# BMC.net
KiCad netlist of a schematic drawn in Altium Designer
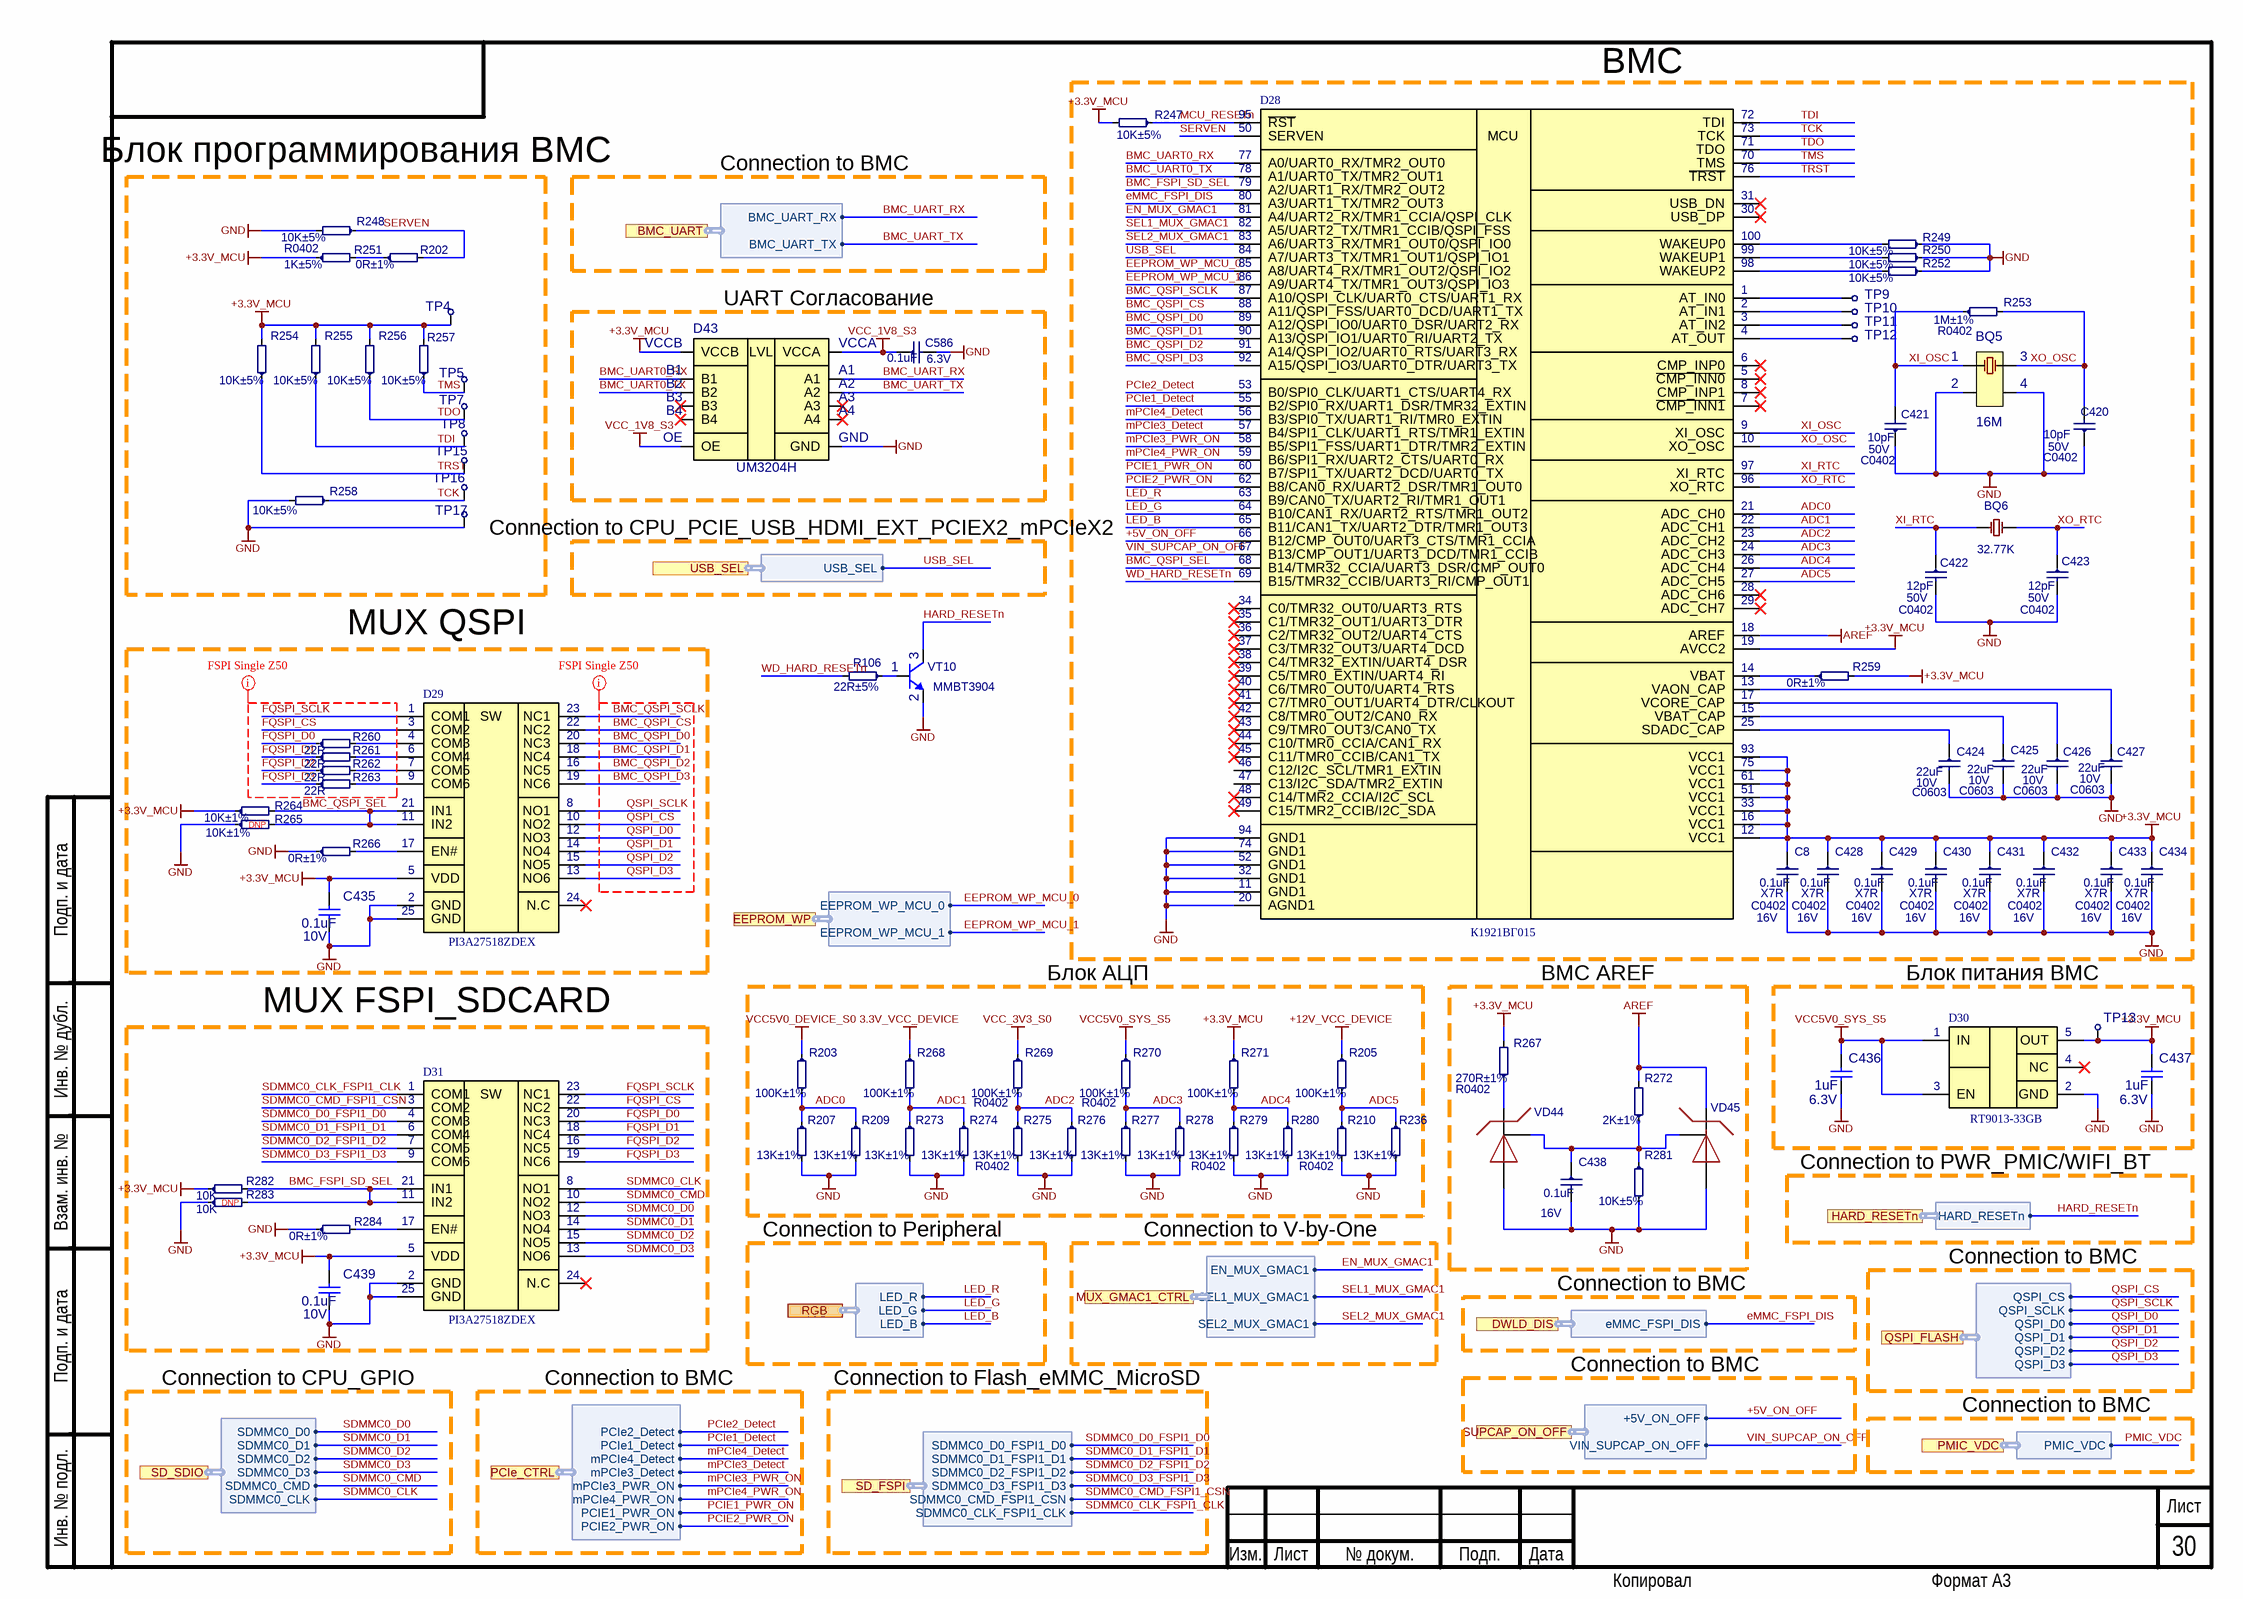
[diagram p0: BMC.SchDoc]

(export (version "E")
  (design (tool "Eeschema 10.0.6"))
  (components
    (comp (ref "BQ5")
      (value "16M")
      (footprint "NX3225GA")
      (description "16MHz 3225 quartz")
      (fields (field (name "PART NUMBER") "X322516MLB4SI") (field (name "TOLERANCE") "30ppm"))
      (libsource (lib "ATB") (part "BQ_4pin_2closed_2.4_2.4"))
    )
    (comp (ref "BQ6")
      (value "32.77K")
      (footprint "FC-12M")
      (description "CRYSTAL 32.768KHZ 12.5PF SMD")
      (fields (field (name "PART NUMBER") "NX2012SA-32.768K-STD-MUB-1") (field (name "MANUFACTURER") "NDK"))
      (libsource (lib "ATB") (part "BQ"))
    )
    (comp (ref "C8")
      (value "0.1uF")
      (footprint "C0402")
      (description "Ceramic Capacitor 0402 100nF ±5% 16V X7R")
      (fields
        (field (name "DIELECTRIC") "X7R")
        (field (name "VOLTAGE") "16V")
        (field (name "CASE") "C0402")
        (field (name "PART NUMBER") "0402-X7R-16V-0.1uF±10%")
        (field (name "TOLERANCE") "10%")
      )
      (libsource (lib "ATB") (part "C"))
    )
    (comp (ref "C420")
      (value "10pF")
      (footprint "C0402")
      (fields
        (field (name "VOLTAGE") "50V")
        (field (name "CASE") "C0402")
        (field (name "PART NUMBER") "0402-NP0-50V-10pF±5%")
        (field (name "TOLERANCE") "5%")
        (field (name "MANUFACTURER") "Yageo")
      )
      (libsource (lib "ATB") (part "C"))
    )
    (comp (ref "C421")
      (value "10pF")
      (footprint "C0402")
      (fields
        (field (name "VOLTAGE") "50V")
        (field (name "CASE") "C0402")
        (field (name "PART NUMBER") "0402-NP0-50V-10pF±5%")
        (field (name "TOLERANCE") "5%")
        (field (name "MANUFACTURER") "Yageo")
      )
      (libsource (lib "ATB") (part "C"))
    )
    (comp (ref "C422")
      (value "12pF")
      (footprint "C0402")
      (fields
        (field (name "VOLTAGE") "50V")
        (field (name "CASE") "C0402")
        (field (name "PART NUMBER") "0402-NP0-50V-12pF±5%")
        (field (name "TOLERANCE") "5%")
        (field (name "MANUFACTURER") "Murata Electronics")
      )
      (libsource (lib "ATB") (part "C"))
    )
    (comp (ref "C423")
      (value "12pF")
      (footprint "C0402")
      (fields
        (field (name "VOLTAGE") "50V")
        (field (name "CASE") "C0402")
        (field (name "PART NUMBER") "0402-NP0-50V-12pF±5%")
        (field (name "TOLERANCE") "5%")
        (field (name "MANUFACTURER") "Murata Electronics")
      )
      (libsource (lib "ATB") (part "C"))
    )
    (comp (ref "C424")
      (value "22uF")
      (footprint "C0603")
      (fields
        (field (name "VOLTAGE") "10V")
        (field (name "CASE") "C0603")
        (field (name "PART NUMBER") "0603-X5R-10V-22uF±20%")
        (field (name "TOLERANCE") "20%")
        (field (name "MANUFACTURER") "Samsung Electro-Mechanics")
      )
      (libsource (lib "ATB") (part "C"))
    )
    (comp (ref "C425")
      (value "22uF")
      (footprint "C0603")
      (fields
        (field (name "VOLTAGE") "10V")
        (field (name "CASE") "C0603")
        (field (name "PART NUMBER") "0603-X5R-10V-22uF±20%")
        (field (name "TOLERANCE") "20%")
        (field (name "MANUFACTURER") "Samsung Electro-Mechanics")
      )
      (libsource (lib "ATB") (part "C"))
    )
    (comp (ref "C426")
      (value "22uF")
      (footprint "C0603")
      (fields
        (field (name "VOLTAGE") "10V")
        (field (name "CASE") "C0603")
        (field (name "PART NUMBER") "0603-X5R-10V-22uF±20%")
        (field (name "TOLERANCE") "20%")
        (field (name "MANUFACTURER") "Samsung Electro-Mechanics")
      )
      (libsource (lib "ATB") (part "C"))
    )
    (comp (ref "C427")
      (value "22uF")
      (footprint "C0603")
      (fields
        (field (name "VOLTAGE") "10V")
        (field (name "CASE") "C0603")
        (field (name "PART NUMBER") "0603-X5R-10V-22uF±20%")
        (field (name "TOLERANCE") "20%")
        (field (name "MANUFACTURER") "Samsung Electro-Mechanics")
      )
      (libsource (lib "ATB") (part "C"))
    )
    (comp (ref "C428")
      (value "0.1uF")
      (footprint "C0402")
      (description "Ceramic Capacitor 0402 100nF ±5% 16V X7R")
      (fields
        (field (name "DIELECTRIC") "X7R")
        (field (name "VOLTAGE") "16V")
        (field (name "CASE") "C0402")
        (field (name "PART NUMBER") "0402-X7R-16V-0.1uF±10%")
        (field (name "TOLERANCE") "10%")
      )
      (libsource (lib "ATB") (part "C"))
    )
    (comp (ref "C429")
      (value "0.1uF")
      (footprint "C0402")
      (description "Ceramic Capacitor 0402 100nF ±5% 16V X7R")
      (fields
        (field (name "DIELECTRIC") "X7R")
        (field (name "VOLTAGE") "16V")
        (field (name "CASE") "C0402")
        (field (name "PART NUMBER") "0402-X7R-16V-0.1uF±10%")
        (field (name "TOLERANCE") "10%")
      )
      (libsource (lib "ATB") (part "C"))
    )
    (comp (ref "C430")
      (value "0.1uF")
      (footprint "C0402")
      (description "Ceramic Capacitor 0402 100nF ±5% 16V X7R")
      (fields
        (field (name "DIELECTRIC") "X7R")
        (field (name "VOLTAGE") "16V")
        (field (name "CASE") "C0402")
        (field (name "PART NUMBER") "0402-X7R-16V-0.1uF±10%")
        (field (name "TOLERANCE") "10%")
      )
      (libsource (lib "ATB") (part "C"))
    )
    (comp (ref "C431")
      (value "0.1uF")
      (footprint "C0402")
      (description "Ceramic Capacitor 0402 100nF ±5% 16V X7R")
      (fields
        (field (name "DIELECTRIC") "X7R")
        (field (name "VOLTAGE") "16V")
        (field (name "CASE") "C0402")
        (field (name "PART NUMBER") "0402-X7R-16V-0.1uF±10%")
        (field (name "TOLERANCE") "10%")
      )
      (libsource (lib "ATB") (part "C"))
    )
    (comp (ref "C432")
      (value "0.1uF")
      (footprint "C0402")
      (description "Ceramic Capacitor 0402 100nF ±5% 16V X7R")
      (fields
        (field (name "DIELECTRIC") "X7R")
        (field (name "VOLTAGE") "16V")
        (field (name "CASE") "C0402")
        (field (name "PART NUMBER") "0402-X7R-16V-0.1uF±10%")
        (field (name "TOLERANCE") "10%")
      )
      (libsource (lib "ATB") (part "C"))
    )
    (comp (ref "C433")
      (value "0.1uF")
      (footprint "C0402")
      (description "Ceramic Capacitor 0402 100nF ±5% 16V X7R")
      (fields
        (field (name "DIELECTRIC") "X7R")
        (field (name "VOLTAGE") "16V")
        (field (name "CASE") "C0402")
        (field (name "PART NUMBER") "0402-X7R-16V-0.1uF±10%")
        (field (name "TOLERANCE") "10%")
      )
      (libsource (lib "ATB") (part "C"))
    )
    (comp (ref "C434")
      (value "0.1uF")
      (footprint "C0402")
      (description "Ceramic Capacitor 0402 100nF ±5% 16V X7R")
      (fields
        (field (name "DIELECTRIC") "X7R")
        (field (name "VOLTAGE") "16V")
        (field (name "CASE") "C0402")
        (field (name "PART NUMBER") "0402-X7R-16V-0.1uF±10%")
        (field (name "TOLERANCE") "10%")
      )
      (libsource (lib "ATB") (part "C"))
    )
    (comp (ref "C435")
      (value "0.1uF")
      (footprint "C0402")
      (fields
        (field (name "PART NUMBER") "0402-X5R-10V-0.1uF±10%")
        (field (name "VOLTAGE") "10V")
        (field (name "TOLERANCE") "10%")
        (field (name "MANUFACTURER") "Yageo")
      )
      (libsource (lib "") (part "C_1"))
    )
    (comp (ref "C436")
      (value "1uF")
      (footprint "C0402")
      (fields
        (field (name "PART NUMBER") "0402-X7R-6.3V-1uF±10%")
        (field (name "VOLTAGE") "6.3V")
        (field (name "TOLERANCE") "10%")
        (field (name "MANUFACTURER") "Yageo")
      )
      (libsource (lib "") (part "C_1"))
    )
    (comp (ref "C437")
      (value "1uF")
      (footprint "C0402")
      (fields
        (field (name "PART NUMBER") "0402-X7R-6.3V-1uF±10%")
        (field (name "VOLTAGE") "6.3V")
        (field (name "TOLERANCE") "10%")
        (field (name "MANUFACTURER") "Yageo")
      )
      (libsource (lib "") (part "C_1"))
    )
    (comp (ref "C438")
      (value "0.1uF")
      (footprint "C0402")
      (description "Ceramic Capacitor 0402 100nF ±5% 16V X7R")
      (fields
        (field (name "VOLTAGE") "16V")
        (field (name "PART NUMBER") "0402-X7R-16V-0.1uF±10%")
        (field (name "TOLERANCE") "10%")
      )
      (libsource (lib "ATB") (part "C"))
    )
    (comp (ref "C439")
      (value "0.1uF")
      (footprint "C0402")
      (fields
        (field (name "PART NUMBER") "0402-X5R-10V-0.1uF±10%")
        (field (name "VOLTAGE") "10V")
        (field (name "TOLERANCE") "10%")
        (field (name "MANUFACTURER") "Yageo")
      )
      (libsource (lib "") (part "C_1"))
    )
    (comp (ref "C586")
      (value "0.1uF")
      (footprint "C0201")
      (fields
        (field (name "VOLTAGE") "6.3V")
        (field (name "PART NUMBER") "0201-X5R-6.3V-0.1uF±10%")
        (field (name "TOLERANCE") "10%")
        (field (name "MANUFACTURER") "Yageo")
      )
      (libsource (lib "ATB") (part "C"))
    )
    (comp (ref "D28")
      (value "К1921ВГ015")
      (footprint "К1921ВГ015")
      (description "32-разрядный ультранизкопотребляющий микроконтроллер RISС-V в пластиковом корпусе.")
      (fields (field (name "MANUFACTURER") "НИИЭТ"))
      (libsource (lib "LIB_RK") (part "К1921ВГ015"))
    )
    (comp (ref "D29")
      (value "PI3A27518ZDEX")
      (footprint "PI3A27518ZDEX")
      (description "1.8/3.3V High-Bandwidth 6-channel, 2:1 Mux/DeMux")
      (fields (field (name "MANUFACTURER") "Diodes Incorporated"))
      (libsource (lib "LIB_RK") (part "PI3A27518ZDEX"))
    )
    (comp (ref "D30")
      (value "RT9013-33GB")
      (footprint "RT9013-25GB")
      (description "Linear Voltage Regulators   500mA 50dB@(10kHz) Fixed 3.3V")
      (fields (field (name "MANUFACTURER") "Richtek"))
      (libsource (lib "LIB_RK") (part "RT9013-25GB"))
    )
    (comp (ref "D31")
      (value "PI3A27518ZDEX")
      (footprint "PI3A27518ZDEX")
      (description "1.8/3.3V High-Bandwidth 6-channel, 2:1 Mux/DeMux")
      (fields (field (name "MANUFACTURER") "Diodes Incorporated"))
      (libsource (lib "LIB_RK") (part "PI3A27518ZDEX"))
    )
    (comp (ref "D43")
      (value "UM3204H")
      (footprint "UM3204H")
      (description "CSP-12(1.4x1.9) Translators, Level Shifters ROHS")
      (fields (field (name "MANUFACTURER") "Union"))
      (libsource (lib "LIB_RK") (part "UM3204H"))
    )
    (comp (ref "R106")
      (value "22R±5%")
      (footprint "R0402")
      (fields
        (field (name "PART NUMBER") "0402-0.0625W-22R-100ppm±5%")
        (field (name "TOLERANCE") "5%")
        (field (name "MANUFACTURER") "Yageo")
      )
      (libsource (lib "ATB") (part "R"))
    )
    (comp (ref "R202")
      (value "0R±1%")
      (footprint "R0402")
      (description "Chip Resistor 0402 0Ω ±1% 50V ±100ppm/℃ Thick Film")
      (fields (field (name "PART NUMBER") "0402-0.0625W-0R-100ppm±1%") (field (name "TOLERANCE") "1%"))
      (libsource (lib "ATB") (part "R"))
    )
    (comp (ref "R203")
      (value "100K±1%")
      (footprint "R0402")
      (description "Chip Resistor 0402 100kΩ ±1% 50V ±100ppm/℃ Thick Film")
      (fields (field (name "PART NUMBER") "0402-0.0625W-100K-100ppm±1%") (field (name "TOLERANCE") "1%"))
      (libsource (lib "ATB") (part "R"))
    )
    (comp (ref "R205")
      (value "100K±1%")
      (footprint "R0402")
      (description "Chip Resistor 0402 100kΩ ±1% 50V ±100ppm/℃ Thick Film")
      (fields (field (name "PART NUMBER") "0402-0.0625W-100K-100ppm±1%") (field (name "TOLERANCE") "1%"))
      (libsource (lib "ATB") (part "R"))
    )
    (comp (ref "R207")
      (value "13K±1%")
      (footprint "R0402")
      (fields
        (field (name "PART NUMBER") "0402-0.0625W-13K-100ppm±1%")
        (field (name "TOLERANCE") "1%")
        (field (name "MANUFACTURER") "Yageo")
      )
      (libsource (lib "ATB") (part "R"))
    )
    (comp (ref "R209")
      (value "13K±1%")
      (footprint "R0402")
      (fields
        (field (name "PART NUMBER") "0402-0.0625W-13K-100ppm±1%")
        (field (name "TOLERANCE") "1%")
        (field (name "MANUFACTURER") "Yageo")
      )
      (libsource (lib "ATB") (part "R"))
    )
    (comp (ref "R210")
      (value "13K±1%")
      (footprint "R0402")
      (fields
        (field (name "CASE") "R0402")
        (field (name "PART NUMBER") "0402-0.0625W-13K-100ppm±1%")
        (field (name "TOLERANCE") "1%")
        (field (name "MANUFACTURER") "Yageo")
      )
      (libsource (lib "ATB") (part "R"))
    )
    (comp (ref "R236")
      (value "13K±1%")
      (footprint "R0402")
      (fields
        (field (name "PART NUMBER") "0402-0.0625W-13K-100ppm±1%")
        (field (name "TOLERANCE") "1%")
        (field (name "MANUFACTURER") "Yageo")
      )
      (libsource (lib "ATB") (part "R"))
    )
    (comp (ref "R247")
      (value "10K±5%")
      (footprint "R0402")
      (fields
        (field (name "PART NUMBER") "0402-0.0625W-10K-100ppm±5%")
        (field (name "TOLERANCE") "5%")
        (field (name "MANUFACTURER") "Yageo")
      )
      (libsource (lib "ATB") (part "R"))
    )
    (comp (ref "R248")
      (value "10K±5%")
      (footprint "R0402")
      (fields
        (field (name "CASE") "R0402")
        (field (name "PART NUMBER") "0402-0.0625W-10K-100ppm±5%")
        (field (name "TOLERANCE") "5%")
        (field (name "MANUFACTURER") "Yageo")
      )
      (libsource (lib "ATB") (part "R"))
    )
    (comp (ref "R249")
      (value "10K±5%")
      (footprint "R0402")
      (fields
        (field (name "PART NUMBER") "0402-0.0625W-10K-100ppm±5%")
        (field (name "TOLERANCE") "5%")
        (field (name "MANUFACTURER") "Yageo")
      )
      (libsource (lib "ATB") (part "R"))
    )
    (comp (ref "R250")
      (value "10K±5%")
      (footprint "R0402")
      (fields
        (field (name "PART NUMBER") "0402-0.0625W-10K-100ppm±5%")
        (field (name "TOLERANCE") "5%")
        (field (name "MANUFACTURER") "Yageo")
      )
      (libsource (lib "ATB") (part "R"))
    )
    (comp (ref "R251")
      (value "1K±5%")
      (footprint "R0402")
      (fields
        (field (name "PART NUMBER") "0402-0.0625W-1K-100ppm±5%")
        (field (name "TOLERANCE") "5%")
        (field (name "MANUFACTURER") "Yageo")
      )
      (libsource (lib "ATB") (part "R"))
    )
    (comp (ref "R252")
      (value "10K±5%")
      (footprint "R0402")
      (fields
        (field (name "PART NUMBER") "0402-0.0625W-10K-100ppm±5%")
        (field (name "TOLERANCE") "5%")
        (field (name "MANUFACTURER") "Yageo")
      )
      (libsource (lib "ATB") (part "R"))
    )
    (comp (ref "R253")
      (value "1M±1%")
      (footprint "R0402")
      (description "Chip Resistor 0402 1MΩ ±1% 50V ±100ppm/℃ Thick Film")
      (fields
        (field (name "CASE") "R0402")
        (field (name "PART NUMBER") "0402-0.0625W-1M-100ppm±1%")
        (field (name "TOLERANCE") "1%")
      )
      (libsource (lib "ATB") (part "R"))
    )
    (comp (ref "R254")
      (value "10K±5%")
      (footprint "R0402")
      (fields
        (field (name "PART NUMBER") "0402-0.0625W-10K-100ppm±5%")
        (field (name "TOLERANCE") "5%")
        (field (name "MANUFACTURER") "Yageo")
      )
      (libsource (lib "ATB") (part "R"))
    )
    (comp (ref "R255")
      (value "10K±5%")
      (footprint "R0402")
      (fields
        (field (name "PART NUMBER") "0402-0.0625W-10K-100ppm±5%")
        (field (name "TOLERANCE") "5%")
        (field (name "MANUFACTURER") "Yageo")
      )
      (libsource (lib "ATB") (part "R"))
    )
    (comp (ref "R256")
      (value "10K±5%")
      (footprint "R0402")
      (fields
        (field (name "PART NUMBER") "0402-0.0625W-10K-100ppm±5%")
        (field (name "TOLERANCE") "5%")
        (field (name "MANUFACTURER") "Yageo")
      )
      (libsource (lib "ATB") (part "R"))
    )
    (comp (ref "R257")
      (value "10K±5%")
      (footprint "R0402")
      (fields
        (field (name "PART NUMBER") "0402-0.0625W-10K-100ppm±5%")
        (field (name "TOLERANCE") "5%")
        (field (name "MANUFACTURER") "Yageo")
      )
      (libsource (lib "ATB") (part "R"))
    )
    (comp (ref "R258")
      (value "10K±5%")
      (footprint "R0402")
      (fields
        (field (name "PART NUMBER") "0402-0.0625W-10K-100ppm±5%")
        (field (name "TOLERANCE") "5%")
        (field (name "MANUFACTURER") "Yageo")
      )
      (libsource (lib "ATB") (part "R"))
    )
    (comp (ref "R259")
      (value "0R±1%")
      (footprint "R0402")
      (description "Chip Resistor 0402 0Ω ±1% 50V ±100ppm/℃ Thick Film")
      (fields (field (name "PART NUMBER") "0402-0.0625W-0R-100ppm±1%") (field (name "TOLERANCE") "1%"))
      (libsource (lib "ATB") (part "R"))
    )
    (comp (ref "R260")
      (value "22R")
      (footprint "R0402")
      (description "Chip Resistor 0402 22Ω ±1% 50V ±100ppm/℃ Thick Film")
      (fields (field (name "PART NUMBER") "0402-0.0625W-22R-100ppm±1%") (field (name "TOLERANCE") "1%"))
      (libsource (lib "ATB") (part "R"))
    )
    (comp (ref "R261")
      (value "22R")
      (footprint "R0402")
      (description "Chip Resistor 0402 22Ω ±1% 50V ±100ppm/℃ Thick Film")
      (fields (field (name "PART NUMBER") "0402-0.0625W-22R-100ppm±1%") (field (name "TOLERANCE") "1%"))
      (libsource (lib "ATB") (part "R"))
    )
    (comp (ref "R262")
      (value "22R")
      (footprint "R0402")
      (description "Chip Resistor 0402 22Ω ±1% 50V ±100ppm/℃ Thick Film")
      (fields (field (name "PART NUMBER") "0402-0.0625W-22R-100ppm±1%") (field (name "TOLERANCE") "1%"))
      (libsource (lib "ATB") (part "R"))
    )
    (comp (ref "R263")
      (value "22R")
      (footprint "R0402")
      (description "Chip Resistor 0402 22Ω ±1% 50V ±100ppm/℃ Thick Film")
      (fields (field (name "PART NUMBER") "0402-0.0625W-22R-100ppm±1%") (field (name "TOLERANCE") "1%"))
      (libsource (lib "ATB") (part "R"))
    )
    (comp (ref "R264")
      (value "10K±1%")
      (footprint "R0402")
      (description "Chip Resistor 0402 10kΩ ±1% 50V ±100ppm/℃ Thick Film")
      (fields (field (name "PART NUMBER") "0402-0.0625W-10K-100ppm±1%") (field (name "TOLERANCE") "1%"))
      (libsource (lib "ATB") (part "R"))
    )
    (comp (ref "R265")
      (value "10K±1%")
      (footprint "R0402")
      (description "Chip Resistor 0402 10kΩ ±1% 50V ±100ppm/℃ Thick Film")
      (fields (field (name "PART NUMBER") "0402-0.0625W-10K-100ppm±1%") (field (name "TOLERANCE") "1%"))
      (libsource (lib "ATB") (part "R"))
    )
    (comp (ref "R266")
      (value "0R±1%")
      (footprint "R0402")
      (description "Chip Resistor 0402 0Ω ±1% 50V ±100ppm/℃ Thick Film")
      (fields (field (name "PART NUMBER") "0402-0.0625W-0R-100ppm±1%") (field (name "TOLERANCE") "1%"))
      (libsource (lib "ATB") (part "R"))
    )
    (comp (ref "R267")
      (value "270R±1%")
      (footprint "R0402")
      (fields
        (field (name "CASE") "R0402")
        (field (name "PART NUMBER") "0402-0.0625W-270R-100ppm±1%")
        (field (name "TOLERANCE") "1%")
        (field (name "MANUFACTURER") "UNI-ROYAL")
      )
      (libsource (lib "ATB") (part "R"))
    )
    (comp (ref "R268")
      (value "100K±1%")
      (footprint "R0402")
      (description "Chip Resistor 0402 100kΩ ±1% 50V ±100ppm/℃ Thick Film")
      (fields (field (name "PART NUMBER") "0402-0.0625W-100K-100ppm±1%") (field (name "TOLERANCE") "1%"))
      (libsource (lib "ATB") (part "R"))
    )
    (comp (ref "R269")
      (value "100K±1%")
      (footprint "R0402")
      (description "Chip Resistor 0402 100kΩ ±1% 50V ±100ppm/℃ Thick Film")
      (fields
        (field (name "CASE") "R0402")
        (field (name "PART NUMBER") "0402-0.0625W-100K-100ppm±1%")
        (field (name "TOLERANCE") "1%")
      )
      (libsource (lib "ATB") (part "R"))
    )
    (comp (ref "R270")
      (value "100K±1%")
      (footprint "R0402")
      (description "Chip Resistor 0402 100kΩ ±1% 50V ±100ppm/℃ Thick Film")
      (fields
        (field (name "CASE") "R0402")
        (field (name "PART NUMBER") "0402-0.0625W-100K-100ppm±1%")
        (field (name "TOLERANCE") "1%")
      )
      (libsource (lib "ATB") (part "R"))
    )
    (comp (ref "R271")
      (value "100K±1%")
      (footprint "R0402")
      (description "Chip Resistor 0402 100kΩ ±1% 50V ±100ppm/℃ Thick Film")
      (fields (field (name "PART NUMBER") "0402-0.0625W-100K-100ppm±1%") (field (name "TOLERANCE") "1%"))
      (libsource (lib "ATB") (part "R"))
    )
    (comp (ref "R272")
      (value "2K±1%")
      (footprint "R0402")
      (fields
        (field (name "PART NUMBER") "0402-0.0625W-2K-100ppm±1%")
        (field (name "TOLERANCE") "1%")
        (field (name "MANUFACTURER") "Yageo")
      )
      (libsource (lib "ATB") (part "R"))
    )
    (comp (ref "R273")
      (value "13K±1%")
      (footprint "R0402")
      (fields
        (field (name "PART NUMBER") "0402-0.0625W-13K-100ppm±1%")
        (field (name "TOLERANCE") "1%")
        (field (name "MANUFACTURER") "Yageo")
      )
      (libsource (lib "ATB") (part "R"))
    )
    (comp (ref "R274")
      (value "13K±1%")
      (footprint "R0402")
      (fields
        (field (name "PART NUMBER") "0402-0.0625W-13K-100ppm±1%")
        (field (name "TOLERANCE") "1%")
        (field (name "MANUFACTURER") "Yageo")
      )
      (libsource (lib "ATB") (part "R"))
    )
    (comp (ref "R275")
      (value "13K±1%")
      (footprint "R0402")
      (fields
        (field (name "CASE") "R0402")
        (field (name "PART NUMBER") "0402-0.0625W-13K-100ppm±1%")
        (field (name "TOLERANCE") "1%")
        (field (name "MANUFACTURER") "Yageo")
      )
      (libsource (lib "ATB") (part "R"))
    )
    (comp (ref "R276")
      (value "13K±1%")
      (footprint "R0402")
      (fields
        (field (name "PART NUMBER") "0402-0.0625W-13K-100ppm±1%")
        (field (name "TOLERANCE") "1%")
        (field (name "MANUFACTURER") "Yageo")
      )
      (libsource (lib "ATB") (part "R"))
    )
    (comp (ref "R277")
      (value "13K±1%")
      (footprint "R0402")
      (fields
        (field (name "PART NUMBER") "0402-0.0625W-13K-100ppm±1%")
        (field (name "TOLERANCE") "1%")
        (field (name "MANUFACTURER") "Yageo")
      )
      (libsource (lib "ATB") (part "R"))
    )
    (comp (ref "R278")
      (value "13K±1%")
      (footprint "R0402")
      (fields
        (field (name "PART NUMBER") "0402-0.0625W-13K-100ppm±1%")
        (field (name "TOLERANCE") "1%")
        (field (name "MANUFACTURER") "Yageo")
      )
      (libsource (lib "ATB") (part "R"))
    )
    (comp (ref "R279")
      (value "13K±1%")
      (footprint "R0402")
      (fields
        (field (name "CASE") "R0402")
        (field (name "PART NUMBER") "0402-0.0625W-13K-100ppm±1%")
        (field (name "TOLERANCE") "1%")
        (field (name "MANUFACTURER") "Yageo")
      )
      (libsource (lib "ATB") (part "R"))
    )
    (comp (ref "R280")
      (value "13K±1%")
      (footprint "R0402")
      (fields
        (field (name "PART NUMBER") "0402-0.0625W-13K-100ppm±1%")
        (field (name "TOLERANCE") "1%")
        (field (name "MANUFACTURER") "Yageo")
      )
      (libsource (lib "ATB") (part "R"))
    )
    (comp (ref "R281")
      (value "10K±5%")
      (footprint "R0402")
      (fields
        (field (name "PART NUMBER") "0402-0.0625W-10K-100ppm±5%")
        (field (name "TOLERANCE") "5%")
        (field (name "MANUFACTURER") "Yageo")
      )
      (libsource (lib "ATB") (part "R"))
    )
    (comp (ref "R282")
      (value "10K")
      (footprint "R0402")
      (description "Chip Resistor 0402 10kΩ ±1% 50V ±100ppm/℃ Thick Film")
      (fields (field (name "PART NUMBER") "0402-0.0625W-10K-100ppm±1%") (field (name "TOLERANCE") "1%"))
      (libsource (lib "ATB") (part "R"))
    )
    (comp (ref "R283")
      (value "10K")
      (footprint "R0402")
      (description "Chip Resistor 0402 10kΩ ±1% 50V ±100ppm/℃ Thick Film")
      (fields (field (name "PART NUMBER") "0402-0.0625W-10K-100ppm±1%") (field (name "TOLERANCE") "1%"))
      (libsource (lib "ATB") (part "R"))
    )
    (comp (ref "R284")
      (value "0R±1%")
      (footprint "R0402")
      (description "Chip Resistor 0402 0Ω ±1% 50V ±100ppm/℃ Thick Film")
      (fields (field (name "PART NUMBER") "0402-0.0625W-0R-100ppm±1%") (field (name "TOLERANCE") "1%"))
      (libsource (lib "ATB") (part "R"))
    )
    (comp (ref "TP4") (value "Тестовая точка") (footprint "TEST") (libsource (lib "ATB") (part "Test")))
    (comp (ref "TP5") (value "Тестовая точка") (footprint "TEST") (libsource (lib "ATB") (part "Test")))
    (comp (ref "TP7") (value "Тестовая точка") (footprint "TEST") (libsource (lib "ATB") (part "Test")))
    (comp (ref "TP8") (value "Тестовая точка") (footprint "TEST") (libsource (lib "ATB") (part "Test")))
    (comp (ref "TP9") (value "Тестовая точка") (footprint "TEST") (libsource (lib "ATB") (part "Test")))
    (comp (ref "TP10") (value "Тестовая точка") (footprint "TEST") (libsource (lib "ATB") (part "Test")))
    (comp (ref "TP11") (value "Тестовая точка") (footprint "TEST") (libsource (lib "ATB") (part "Test")))
    (comp (ref "TP12") (value "Тестовая точка") (footprint "TEST") (libsource (lib "ATB") (part "Test")))
    (comp (ref "TP13") (value "Тестовая точка") (footprint "TEST") (libsource (lib "ATB") (part "Test")))
    (comp (ref "TP15") (value "Тестовая точка") (footprint "TEST") (libsource (lib "ATB") (part "Test")))
    (comp (ref "TP16") (value "Тестовая точка") (footprint "TEST") (libsource (lib "ATB") (part "Test")))
    (comp (ref "TP17") (value "Тестовая точка") (footprint "TEST") (libsource (lib "ATB") (part "Test")))
    (comp (ref "VD44")
      (value "TL431AIDBZR")
      (footprint "TL431AIDBZR")
      (fields (field (name "MANUFACTURER") "TI"))
      (libsource (lib "LIB_RK") (part "TL431AIDBZR"))
    )
    (comp (ref "VD45")
      (value "TL432AIDBZR")
      (footprint "TL432AIDBZR")
      (fields (field (name "MANUFACTURER") "TI"))
      (libsource (lib "LIB_RK") (part "TL432AIDBZR"))
    )
    (comp (ref "VT10")
      (value "MMBT3904")
      (footprint "SOT23")
      (description "NPN transistor")
      (fields (field (name "VOLTAGE") "40V") (field (name "MANUFACTURER") "Diotec Semiconductor"))
      (libsource (lib "ATB") (part "BC846BLT1G"))
    )
  )
  (nets
    (net (code "11") (name "+3.3V_MCU") (class "Default")
      (node (ref "C428") (pin "1") (pinfunction "1_1") (pintype "passive"))
      (node (ref "C429") (pin "1") (pinfunction "1_1") (pintype "passive"))
      (node (ref "C430") (pin "1") (pinfunction "1_1") (pintype "passive"))
      (node (ref "C431") (pin "1") (pinfunction "1_1") (pintype "passive"))
      (node (ref "C432") (pin "1") (pinfunction "1_1") (pintype "passive"))
      (node (ref "C433") (pin "1") (pinfunction "1_1") (pintype "passive"))
      (node (ref "C434") (pin "1") (pinfunction "1_1") (pintype "passive"))
      (node (ref "C435") (pin "2") (pinfunction "2_2") (pintype "passive"))
      (node (ref "C437") (pin "2") (pinfunction "2_2") (pintype "passive"))
      (node (ref "C439") (pin "2") (pinfunction "2_2") (pintype "passive"))
      (node (ref "C8") (pin "1") (pinfunction "1_1") (pintype "passive"))
      (node (ref "D28") (pin "12") (pinfunction "VCC1_12") (pintype "passive"))
      (node (ref "D28") (pin "16") (pinfunction "VCC1_16") (pintype "passive"))
      (node (ref "D28") (pin "19") (pinfunction "AVCC2_19") (pintype "passive"))
      (node (ref "D28") (pin "33") (pinfunction "VCC1_33") (pintype "passive"))
      (node (ref "D28") (pin "51") (pinfunction "VCC1_51") (pintype "passive"))
      (node (ref "D28") (pin "61") (pinfunction "VCC1_61") (pintype "passive"))
      (node (ref "D28") (pin "75") (pinfunction "VCC1_75") (pintype "passive"))
      (node (ref "D28") (pin "93") (pinfunction "VCC1_93") (pintype "passive"))
      (node (ref "D29") (pin "5") (pinfunction "VDD_5") (pintype "passive"))
      (node (ref "D30") (pin "5") (pinfunction "OUT_5") (pintype "passive"))
      (node (ref "D31") (pin "5") (pinfunction "VDD_5") (pintype "passive"))
      (node (ref "D43") (pin "VCCB") (pinfunction "VCCB_VCCB") (pintype "passive"))
      (node (ref "R247") (pin "2") (pinfunction "2_2") (pintype "passive"))
      (node (ref "R251") (pin "1") (pinfunction "1_1") (pintype "passive"))
      (node (ref "R254") (pin "2") (pinfunction "2_2") (pintype "passive"))
      (node (ref "R255") (pin "2") (pinfunction "2_2") (pintype "passive"))
      (node (ref "R256") (pin "2") (pinfunction "2_2") (pintype "passive"))
      (node (ref "R257") (pin "2") (pinfunction "2_2") (pintype "passive"))
      (node (ref "R259") (pin "2") (pinfunction "2_2") (pintype "passive"))
      (node (ref "R264") (pin "1") (pinfunction "1_1") (pintype "passive"))
      (node (ref "R267") (pin "2") (pinfunction "2_2") (pintype "passive"))
      (node (ref "R271") (pin "1") (pinfunction "1_1") (pintype "passive"))
      (node (ref "R282") (pin "1") (pinfunction "1_1") (pintype "passive"))
      (node (ref "TP13") (pin "1") (pinfunction "1_1") (pintype "passive"))
      (node (ref "TP4") (pin "1") (pinfunction "1_1") (pintype "passive"))
    )
    (net (code "12") (name "+12V_VCC_DEVICE") (class "Default")
      (node (ref "R205") (pin "1") (pinfunction "1_1") (pintype "passive"))
    )
    (net (code "13") (name "/+5V_ON_OFF") (class "Default")
      (node (ref "D28") (pin "66") (pinfunction "B12/CMP_OUT0/UART3_CTS/TMR1_CCIA_66") (pintype "passive"))
    )
    (net (code "14") (name "/ADC0") (class "Default")
      (node (ref "D28") (pin "21") (pinfunction "ADC_CH0_21") (pintype "passive"))
      (node (ref "R203") (pin "2") (pinfunction "2_2") (pintype "passive"))
      (node (ref "R207") (pin "1") (pinfunction "1_1") (pintype "passive"))
      (node (ref "R209") (pin "1") (pinfunction "1_1") (pintype "passive"))
    )
    (net (code "15") (name "/ADC1") (class "Default")
      (node (ref "D28") (pin "22") (pinfunction "ADC_CH1_22") (pintype "passive"))
      (node (ref "R268") (pin "2") (pinfunction "2_2") (pintype "passive"))
      (node (ref "R273") (pin "1") (pinfunction "1_1") (pintype "passive"))
      (node (ref "R274") (pin "1") (pinfunction "1_1") (pintype "passive"))
    )
    (net (code "16") (name "/ADC2") (class "Default")
      (node (ref "D28") (pin "23") (pinfunction "ADC_CH2_23") (pintype "passive"))
      (node (ref "R269") (pin "2") (pinfunction "2_2") (pintype "passive"))
      (node (ref "R275") (pin "1") (pinfunction "1_1") (pintype "passive"))
      (node (ref "R276") (pin "1") (pinfunction "1_1") (pintype "passive"))
    )
    (net (code "17") (name "/ADC3") (class "Default")
      (node (ref "D28") (pin "24") (pinfunction "ADC_CH3_24") (pintype "passive"))
      (node (ref "R270") (pin "2") (pinfunction "2_2") (pintype "passive"))
      (node (ref "R277") (pin "1") (pinfunction "1_1") (pintype "passive"))
      (node (ref "R278") (pin "1") (pinfunction "1_1") (pintype "passive"))
    )
    (net (code "18") (name "/ADC4") (class "Default")
      (node (ref "D28") (pin "26") (pinfunction "ADC_CH4_26") (pintype "passive"))
      (node (ref "R271") (pin "2") (pinfunction "2_2") (pintype "passive"))
      (node (ref "R279") (pin "1") (pinfunction "1_1") (pintype "passive"))
      (node (ref "R280") (pin "1") (pinfunction "1_1") (pintype "passive"))
    )
    (net (code "19") (name "/ADC5") (class "Default")
      (node (ref "D28") (pin "27") (pinfunction "ADC_CH5_27") (pintype "passive"))
      (node (ref "R205") (pin "2") (pinfunction "2_2") (pintype "passive"))
      (node (ref "R210") (pin "1") (pinfunction "1_1") (pintype "passive"))
      (node (ref "R236") (pin "1") (pinfunction "1_1") (pintype "passive"))
    )
    (net (code "20") (name "/BMC_FSPI_SD_SEL") (class "Default")
      (node (ref "D28") (pin "79") (pinfunction "A2/UART1_RX/TMR2_OUT2_79") (pintype "passive"))
      (node (ref "D31") (pin "11") (pinfunction "IN2_11") (pintype "passive"))
      (node (ref "D31") (pin "21") (pinfunction "IN1_21") (pintype "passive"))
      (node (ref "R282") (pin "2") (pinfunction "2_2") (pintype "passive"))
      (node (ref "R283") (pin "2") (pinfunction "2_2") (pintype "passive"))
    )
    (net (code "21") (name "/BMC_QSPI_CS") (class "Default")
      (node (ref "D28") (pin "88") (pinfunction "A11/QSPI_FSS/UART0_DCD/UART1_TX_88") (pintype "passive"))
      (node (ref "D29") (pin "22") (pinfunction "NC2_22") (pintype "passive"))
    )
    (net (code "22") (name "/BMC_QSPI_D0") (class "Default")
      (node (ref "D28") (pin "89") (pinfunction "A12/QSPI_IO0/UART0_DSR/UART2_RX_89") (pintype "passive"))
      (node (ref "D29") (pin "20") (pinfunction "NC3_20") (pintype "passive"))
    )
    (net (code "23") (name "/BMC_QSPI_D1") (class "Default")
      (node (ref "D28") (pin "90") (pinfunction "A13/QSPI_IO1/UART0_RI/UART2_TX_90") (pintype "passive"))
      (node (ref "D29") (pin "18") (pinfunction "NC4_18") (pintype "passive"))
    )
    (net (code "24") (name "/BMC_QSPI_D2") (class "Default")
      (node (ref "D28") (pin "91") (pinfunction "A14/QSPI_IO2/UART0_RTS/UART3_RX_91") (pintype "passive"))
      (node (ref "D29") (pin "16") (pinfunction "NC5_16") (pintype "passive"))
    )
    (net (code "25") (name "/BMC_QSPI_D3") (class "Default")
      (node (ref "D28") (pin "92") (pinfunction "A15/QSPI_IO3/UART0_DTR/UART3_TX_92") (pintype "passive"))
      (node (ref "D29") (pin "19") (pinfunction "NC6_19") (pintype "passive"))
    )
    (net (code "26") (name "/BMC_QSPI_SCLK") (class "Default")
      (node (ref "D28") (pin "87") (pinfunction "A10/QSPI_CLK/UART0_CTS/UART1_RX_87") (pintype "passive"))
      (node (ref "D29") (pin "23") (pinfunction "NC1_23") (pintype "passive"))
    )
    (net (code "27") (name "/BMC_QSPI_SEL") (class "Default")
      (node (ref "D28") (pin "68") (pinfunction "B14/TMR32_CCIA/UART3_DSR/CMP_OUT0_68") (pintype "passive"))
      (node (ref "D29") (pin "11") (pinfunction "IN2_11") (pintype "passive"))
      (node (ref "D29") (pin "21") (pinfunction "IN1_21") (pintype "passive"))
      (node (ref "R264") (pin "2") (pinfunction "2_2") (pintype "passive"))
      (node (ref "R265") (pin "2") (pinfunction "2_2") (pintype "passive"))
    )
    (net (code "28") (name "/BMC_UART0_RX") (class "Default")
      (node (ref "D28") (pin "77") (pinfunction "A0/UART0_RX/TMR2_OUT0_77") (pintype "passive"))
      (node (ref "D43") (pin "B1") (pinfunction "B1_B1") (pintype "passive"))
    )
    (net (code "29") (name "/BMC_UART0_TX") (class "Default")
      (node (ref "D28") (pin "78") (pinfunction "A1/UART0_TX/TMR2_OUT1_78") (pintype "passive"))
      (node (ref "D43") (pin "B2") (pinfunction "B2_B2") (pintype "passive"))
    )
    (net (code "30") (name "/BMC_UART_RX") (class "Default")
      (node (ref "D43") (pin "A1") (pinfunction "A1_A1") (pintype "passive"))
    )
    (net (code "31") (name "/BMC_UART_TX") (class "Default")
      (node (ref "D43") (pin "A2") (pinfunction "A2_A2") (pintype "passive"))
    )
    (net (code "32") (name "/EEPROM_WP_MCU_0") (class "Default")
      (node (ref "D28") (pin "85") (pinfunction "A8/UART4_RX/TMR1_OUT2/QSPI_IO2_85") (pintype "passive"))
    )
    (net (code "33") (name "/EEPROM_WP_MCU_1") (class "Default")
      (node (ref "D28") (pin "86") (pinfunction "A9/UART4_TX/TMR1_OUT3/QSPI_IO3_86") (pintype "passive"))
    )
    (net (code "34") (name "/EN_MUX_GMAC1") (class "Default")
      (node (ref "D28") (pin "81") (pinfunction "A4/UART2_RX/TMR1_CCIA/QSPI_CLK_81") (pintype "passive"))
    )
    (net (code "35") (name "/FQSPI_CS") (class "Default")
      (node (ref "D29") (pin "3") (pinfunction "COM2_3") (pintype "passive"))
      (node (ref "D31") (pin "22") (pinfunction "NC2_22") (pintype "passive"))
    )
    (net (code "36") (name "/FQSPI_D0") (class "Default")
      (node (ref "D31") (pin "20") (pinfunction "NC3_20") (pintype "passive"))
      (node (ref "R260") (pin "1") (pinfunction "1_1") (pintype "passive"))
    )
    (net (code "37") (name "/FQSPI_D1") (class "Default")
      (node (ref "D31") (pin "18") (pinfunction "NC4_18") (pintype "passive"))
      (node (ref "R261") (pin "1") (pinfunction "1_1") (pintype "passive"))
    )
    (net (code "38") (name "/FQSPI_D2") (class "Default")
      (node (ref "D31") (pin "16") (pinfunction "NC5_16") (pintype "passive"))
      (node (ref "R262") (pin "1") (pinfunction "1_1") (pintype "passive"))
    )
    (net (code "39") (name "/FQSPI_D3") (class "Default")
      (node (ref "D31") (pin "19") (pinfunction "NC6_19") (pintype "passive"))
      (node (ref "R263") (pin "1") (pinfunction "1_1") (pintype "passive"))
    )
    (net (code "40") (name "/FQSPI_SCLK") (class "Default")
      (node (ref "D29") (pin "1") (pinfunction "COM1_1") (pintype "passive"))
      (node (ref "D31") (pin "23") (pinfunction "NC1_23") (pintype "passive"))
    )
    (net (code "41") (name "/HARD_RESETn") (class "Default")
      (node (ref "VT10") (pin "3") (pinfunction "C_3") (pintype "passive"))
    )
    (net (code "42") (name "/LED_B") (class "Default")
      (node (ref "D28") (pin "65") (pinfunction "B11/CAN1_TX/UART2_DTR/TMR1_OUT3_65") (pintype "passive"))
    )
    (net (code "43") (name "/LED_G") (class "Default")
      (node (ref "D28") (pin "64") (pinfunction "B10/CAN1_RX/UART2_RTS/TMR1_OUT2_64") (pintype "passive"))
    )
    (net (code "44") (name "/LED_R") (class "Default")
      (node (ref "D28") (pin "63") (pinfunction "B9/CAN0_TX/UART2_RI/TMR1_OUT1_63") (pintype "passive"))
    )
    (net (code "45") (name "/MCU_RESETn") (class "Default")
      (node (ref "D28") (pin "95") (pinfunction "~{RST}_95") (pintype "passive"))
      (node (ref "R247") (pin "1") (pinfunction "1_1") (pintype "passive"))
    )
    (net (code "46") (name "/PCIE1_PWR_ON") (class "Default")
      (node (ref "D28") (pin "60") (pinfunction "B7/SPI1_TX/UART2_DCD/UART0_TX_60") (pintype "passive"))
    )
    (net (code "47") (name "/PCIE2_PWR_ON") (class "Default")
      (node (ref "D28") (pin "62") (pinfunction "B8/CAN0_RX/UART2_DSR/TMR1_OUT0_62") (pintype "passive"))
    )
    (net (code "48") (name "/PCIe1_Detect") (class "Default")
      (node (ref "D28") (pin "55") (pinfunction "B2/SPI0_RX/UART1_DSR/TMR32_EXTIN_55") (pintype "passive"))
    )
    (net (code "49") (name "/PCIe2_Detect") (class "Default")
      (node (ref "D28") (pin "53") (pinfunction "B0/SPI0_CLK/UART1_CTS/UART4_RX_53") (pintype "passive"))
    )
    (net (code "51") (name "/QSPI_CS") (class "Default")
      (node (ref "D29") (pin "10") (pinfunction "NO2_10") (pintype "passive"))
    )
    (net (code "52") (name "/QSPI_D0") (class "Default")
      (node (ref "D29") (pin "12") (pinfunction "NO3_12") (pintype "passive"))
    )
    (net (code "53") (name "/QSPI_D1") (class "Default")
      (node (ref "D29") (pin "14") (pinfunction "NO4_14") (pintype "passive"))
    )
    (net (code "54") (name "/QSPI_D2") (class "Default")
      (node (ref "D29") (pin "15") (pinfunction "NO5_15") (pintype "passive"))
    )
    (net (code "55") (name "/QSPI_D3") (class "Default")
      (node (ref "D29") (pin "13") (pinfunction "NO6_13") (pintype "passive"))
    )
    (net (code "56") (name "/QSPI_SCLK") (class "Default")
      (node (ref "D29") (pin "8") (pinfunction "NO1_8") (pintype "passive"))
    )
    (net (code "57") (name "/SDMMC0_CLK") (class "Default")
      (node (ref "D31") (pin "8") (pinfunction "NO1_8") (pintype "passive"))
    )
    (net (code "58") (name "/SDMMC0_CLK_FSPI1_CLK") (class "Default")
      (node (ref "D31") (pin "1") (pinfunction "COM1_1") (pintype "passive"))
    )
    (net (code "59") (name "/SDMMC0_CMD") (class "Default")
      (node (ref "D31") (pin "10") (pinfunction "NO2_10") (pintype "passive"))
    )
    (net (code "60") (name "/SDMMC0_CMD_FSPI1_CSN") (class "Default")
      (node (ref "D31") (pin "3") (pinfunction "COM2_3") (pintype "passive"))
    )
    (net (code "61") (name "/SDMMC0_D0") (class "Default")
      (node (ref "D31") (pin "12") (pinfunction "NO3_12") (pintype "passive"))
    )
    (net (code "62") (name "/SDMMC0_D0_FSPI1_D0") (class "Default")
      (node (ref "D31") (pin "4") (pinfunction "COM3_4") (pintype "passive"))
    )
    (net (code "63") (name "/SDMMC0_D1") (class "Default")
      (node (ref "D31") (pin "14") (pinfunction "NO4_14") (pintype "passive"))
    )
    (net (code "64") (name "/SDMMC0_D1_FSPI1_D1") (class "Default")
      (node (ref "D31") (pin "6") (pinfunction "COM4_6") (pintype "passive"))
    )
    (net (code "65") (name "/SDMMC0_D2") (class "Default")
      (node (ref "D31") (pin "15") (pinfunction "NO5_15") (pintype "passive"))
    )
    (net (code "66") (name "/SDMMC0_D2_FSPI1_D2") (class "Default")
      (node (ref "D31") (pin "7") (pinfunction "COM5_7") (pintype "passive"))
    )
    (net (code "67") (name "/SDMMC0_D3") (class "Default")
      (node (ref "D31") (pin "13") (pinfunction "NO6_13") (pintype "passive"))
    )
    (net (code "68") (name "/SDMMC0_D3_FSPI1_D3") (class "Default")
      (node (ref "D31") (pin "9") (pinfunction "COM6_9") (pintype "passive"))
    )
    (net (code "69") (name "/SEL1_MUX_GMAC1") (class "Default")
      (node (ref "D28") (pin "82") (pinfunction "A5/UART2_TX/TMR1_CCIB/QSPI_FSS_82") (pintype "passive"))
    )
    (net (code "70") (name "/SEL2_MUX_GMAC1") (class "Default")
      (node (ref "D28") (pin "83") (pinfunction "A6/UART3_RX/TMR1_OUT0/QSPI_IO0_83") (pintype "passive"))
    )
    (net (code "71") (name "/SERVEN") (class "Default")
      (node (ref "D28") (pin "50") (pinfunction "SERVEN_50") (pintype "passive"))
      (node (ref "R202") (pin "2") (pinfunction "2_2") (pintype "passive"))
      (node (ref "R248") (pin "1") (pinfunction "1_1") (pintype "passive"))
    )
    (net (code "72") (name "/TCK") (class "Default")
      (node (ref "D28") (pin "73") (pinfunction "TCK_73") (pintype "passive"))
      (node (ref "R258") (pin "1") (pinfunction "1_1") (pintype "passive"))
      (node (ref "TP16") (pin "1") (pinfunction "1_1") (pintype "passive"))
    )
    (net (code "73") (name "/TDI") (class "Default")
      (node (ref "D28") (pin "72") (pinfunction "TDI_72") (pintype "passive"))
      (node (ref "R255") (pin "1") (pinfunction "1_1") (pintype "passive"))
      (node (ref "TP8") (pin "1") (pinfunction "1_1") (pintype "passive"))
    )
    (net (code "74") (name "/TDO") (class "Default")
      (node (ref "D28") (pin "71") (pinfunction "TDO_71") (pintype "passive"))
      (node (ref "R256") (pin "1") (pinfunction "1_1") (pintype "passive"))
      (node (ref "TP7") (pin "1") (pinfunction "1_1") (pintype "passive"))
    )
    (net (code "75") (name "/TMS") (class "Default")
      (node (ref "D28") (pin "70") (pinfunction "TMS_70") (pintype "passive"))
      (node (ref "R257") (pin "1") (pinfunction "1_1") (pintype "passive"))
      (node (ref "TP5") (pin "1") (pinfunction "1_1") (pintype "passive"))
    )
    (net (code "76") (name "/TRST") (class "Default")
      (node (ref "D28") (pin "76") (pinfunction "~{TRST}_76") (pintype "passive"))
      (node (ref "R254") (pin "1") (pinfunction "1_1") (pintype "passive"))
      (node (ref "TP15") (pin "1") (pinfunction "1_1") (pintype "passive"))
    )
    (net (code "77") (name "/USB_SEL") (class "Default")
      (node (ref "D28") (pin "84") (pinfunction "A7/UART3_TX/TMR1_OUT1/QSPI_IO1_84") (pintype "passive"))
    )
    (net (code "78") (name "/VIN_SUPCAP_ON_OFF") (class "Default")
      (node (ref "D28") (pin "67") (pinfunction "B13/CMP_OUT1/UART3_DCD/TMR1_CCIB_67") (pintype "passive"))
    )
    (net (code "79") (name "/WD_HARD_RESETn") (class "Default")
      (node (ref "D28") (pin "69") (pinfunction "B15/TMR32_CCIB/UART3_RI/CMP_OUT1_69") (pintype "passive"))
      (node (ref "R106") (pin "2") (pinfunction "2_2") (pintype "passive"))
    )
    (net (code "80") (name "/XI_OSC") (class "Default")
      (node (ref "BQ5") (pin "1") (pinfunction "1_1") (pintype "passive"))
      (node (ref "C421") (pin "2") (pinfunction "2_2") (pintype "passive"))
      (node (ref "D28") (pin "9") (pinfunction "XI_OSC_9") (pintype "passive"))
      (node (ref "R253") (pin "1") (pinfunction "1_1") (pintype "passive"))
    )
    (net (code "81") (name "/XI_RTC") (class "Default")
      (node (ref "BQ6") (pin "1") (pinfunction "inp_1") (pintype "passive"))
      (node (ref "C422") (pin "1") (pinfunction "1_1") (pintype "passive"))
      (node (ref "D28") (pin "97") (pinfunction "XI_RTC_97") (pintype "passive"))
    )
    (net (code "82") (name "/XO_OSC") (class "Default")
      (node (ref "BQ5") (pin "3") (pinfunction "3_3") (pintype "passive"))
      (node (ref "C420") (pin "2") (pinfunction "2_2") (pintype "passive"))
      (node (ref "D28") (pin "10") (pinfunction "XO_OSC_10") (pintype "passive"))
      (node (ref "R253") (pin "2") (pinfunction "2_2") (pintype "passive"))
    )
    (net (code "83") (name "/XO_RTC") (class "Default")
      (node (ref "BQ6") (pin "2") (pinfunction "out_2") (pintype "passive"))
      (node (ref "C423") (pin "1") (pinfunction "1_1") (pintype "passive"))
      (node (ref "D28") (pin "96") (pinfunction "XO_RTC_96") (pintype "passive"))
    )
    (net (code "84") (name "/eMMC_FSPI_DIS") (class "Default")
      (node (ref "D28") (pin "80") (pinfunction "A3/UART1_TX/TMR2_OUT3_80") (pintype "passive"))
    )
    (net (code "85") (name "/mPCIe3_Detect") (class "Default")
      (node (ref "D28") (pin "57") (pinfunction "B4/SPI1_CLK/UART1_RTS/TMR1_EXTIN_57") (pintype "passive"))
    )
    (net (code "86") (name "/mPCIe3_PWR_ON") (class "Default")
      (node (ref "D28") (pin "58") (pinfunction "B5/SPI1_FSS/UART1_DTR/TMR2_EXTIN_58") (pintype "passive"))
    )
    (net (code "87") (name "/mPCIe4_Detect") (class "Default")
      (node (ref "D28") (pin "56") (pinfunction "B3/SPI0_TX/UART1_RI/TMR0_EXTIN_56") (pintype "passive"))
    )
    (net (code "88") (name "/mPCIe4_PWR_ON") (class "Default")
      (node (ref "D28") (pin "59") (pinfunction "B6/SPI1_RX/UART2_CTS/UART0_RX_59") (pintype "passive"))
    )
    (net (code "102") (name "3.3V_VCC_DEVICE") (class "Default")
      (node (ref "R268") (pin "1") (pinfunction "1_1") (pintype "passive"))
    )
    (net (code "103") (name "AREF") (class "Default")
      (node (ref "D28") (pin "18") (pinfunction "AREF_18") (pintype "passive"))
      (node (ref "R272") (pin "2") (pinfunction "2_2") (pintype "passive"))
      (node (ref "VD45") (pin "2") (pinfunction "K_2") (pintype "passive"))
    )
    (net (code "104") (name "GND") (class "Default")
      (node (ref "BQ5") (pin "2") (pinfunction "2_2") (pintype "passive"))
      (node (ref "BQ5") (pin "4") (pinfunction "4_4") (pintype "passive"))
      (node (ref "C420") (pin "1") (pinfunction "1_1") (pintype "passive"))
      (node (ref "C421") (pin "1") (pinfunction "1_1") (pintype "passive"))
      (node (ref "C422") (pin "2") (pinfunction "2_2") (pintype "passive"))
      (node (ref "C423") (pin "2") (pinfunction "2_2") (pintype "passive"))
      (node (ref "C424") (pin "2") (pinfunction "2_2") (pintype "passive"))
      (node (ref "C425") (pin "2") (pinfunction "2_2") (pintype "passive"))
      (node (ref "C426") (pin "2") (pinfunction "2_2") (pintype "passive"))
      (node (ref "C427") (pin "2") (pinfunction "2_2") (pintype "passive"))
      (node (ref "C428") (pin "2") (pinfunction "2_2") (pintype "passive"))
      (node (ref "C429") (pin "2") (pinfunction "2_2") (pintype "passive"))
      (node (ref "C430") (pin "2") (pinfunction "2_2") (pintype "passive"))
      (node (ref "C431") (pin "2") (pinfunction "2_2") (pintype "passive"))
      (node (ref "C432") (pin "2") (pinfunction "2_2") (pintype "passive"))
      (node (ref "C433") (pin "2") (pinfunction "2_2") (pintype "passive"))
      (node (ref "C434") (pin "2") (pinfunction "2_2") (pintype "passive"))
      (node (ref "C435") (pin "1") (pinfunction "1_1") (pintype "passive"))
      (node (ref "C436") (pin "1") (pinfunction "1_1") (pintype "passive"))
      (node (ref "C437") (pin "1") (pinfunction "1_1") (pintype "passive"))
      (node (ref "C438") (pin "2") (pinfunction "2_2") (pintype "passive"))
      (node (ref "C439") (pin "1") (pinfunction "1_1") (pintype "passive"))
      (node (ref "C586") (pin "2") (pinfunction "2_2") (pintype "passive"))
      (node (ref "C8") (pin "2") (pinfunction "2_2") (pintype "passive"))
      (node (ref "D28") (pin "11") (pinfunction "GND1_11") (pintype "passive"))
      (node (ref "D28") (pin "20") (pinfunction "AGND1_20") (pintype "passive"))
      (node (ref "D28") (pin "32") (pinfunction "GND1_32") (pintype "passive"))
      (node (ref "D28") (pin "52") (pinfunction "GND1_52") (pintype "passive"))
      (node (ref "D28") (pin "74") (pinfunction "GND1_74") (pintype "passive"))
      (node (ref "D28") (pin "94") (pinfunction "GND1_94") (pintype "passive"))
      (node (ref "D29") (pin "2") (pinfunction "GND_2") (pintype "passive"))
      (node (ref "D29") (pin "25") (pinfunction "GND_25") (pintype "passive"))
      (node (ref "D30") (pin "2") (pinfunction "GND_2") (pintype "passive"))
      (node (ref "D31") (pin "2") (pinfunction "GND_2") (pintype "passive"))
      (node (ref "D31") (pin "25") (pinfunction "GND_25") (pintype "passive"))
      (node (ref "D43") (pin "GND") (pinfunction "GND_GND") (pintype "passive"))
      (node (ref "R207") (pin "2") (pinfunction "2_2") (pintype "passive"))
      (node (ref "R209") (pin "2") (pinfunction "2_2") (pintype "passive"))
      (node (ref "R210") (pin "2") (pinfunction "2_2") (pintype "passive"))
      (node (ref "R236") (pin "2") (pinfunction "2_2") (pintype "passive"))
      (node (ref "R248") (pin "2") (pinfunction "2_2") (pintype "passive"))
      (node (ref "R249") (pin "1") (pinfunction "1_1") (pintype "passive"))
      (node (ref "R250") (pin "1") (pinfunction "1_1") (pintype "passive"))
      (node (ref "R252") (pin "1") (pinfunction "1_1") (pintype "passive"))
      (node (ref "R258") (pin "2") (pinfunction "2_2") (pintype "passive"))
      (node (ref "R265") (pin "1") (pinfunction "1_1") (pintype "passive"))
      (node (ref "R266") (pin "1") (pinfunction "1_1") (pintype "passive"))
      (node (ref "R273") (pin "2") (pinfunction "2_2") (pintype "passive"))
      (node (ref "R274") (pin "2") (pinfunction "2_2") (pintype "passive"))
      (node (ref "R275") (pin "2") (pinfunction "2_2") (pintype "passive"))
      (node (ref "R276") (pin "2") (pinfunction "2_2") (pintype "passive"))
      (node (ref "R277") (pin "2") (pinfunction "2_2") (pintype "passive"))
      (node (ref "R278") (pin "2") (pinfunction "2_2") (pintype "passive"))
      (node (ref "R279") (pin "2") (pinfunction "2_2") (pintype "passive"))
      (node (ref "R280") (pin "2") (pinfunction "2_2") (pintype "passive"))
      (node (ref "R281") (pin "2") (pinfunction "2_2") (pintype "passive"))
      (node (ref "R283") (pin "1") (pinfunction "1_1") (pintype "passive"))
      (node (ref "R284") (pin "1") (pinfunction "1_1") (pintype "passive"))
      (node (ref "TP17") (pin "1") (pinfunction "1_1") (pintype "passive"))
      (node (ref "VD44") (pin "3") (pinfunction "A_3") (pintype "passive"))
      (node (ref "VD45") (pin "3") (pinfunction "A_3") (pintype "passive"))
      (node (ref "VT10") (pin "2") (pinfunction "E_2") (pintype "passive"))
    )
    (net (code "105") (name "Net-(D28-AT_IN0)") (class "Default")
      (node (ref "D28") (pin "1") (pinfunction "AT_IN0_1") (pintype "passive"))
      (node (ref "TP9") (pin "1") (pinfunction "1_1") (pintype "passive"))
    )
    (net (code "106") (name "Net-(D28-AT_IN1)") (class "Default")
      (node (ref "D28") (pin "2") (pinfunction "AT_IN1_2") (pintype "passive"))
      (node (ref "TP10") (pin "1") (pinfunction "1_1") (pintype "passive"))
    )
    (net (code "107") (name "Net-(D28-AT_IN2)") (class "Default")
      (node (ref "D28") (pin "3") (pinfunction "AT_IN2_3") (pintype "passive"))
      (node (ref "TP11") (pin "1") (pinfunction "1_1") (pintype "passive"))
    )
    (net (code "108") (name "Net-(D28-AT_OUT)") (class "Default")
      (node (ref "D28") (pin "4") (pinfunction "AT_OUT_4") (pintype "passive"))
      (node (ref "TP12") (pin "1") (pinfunction "1_1") (pintype "passive"))
    )
    (net (code "109") (name "Net-(D28-SDADC_CAP)") (class "Default")
      (node (ref "C424") (pin "1") (pinfunction "1_1") (pintype "passive"))
      (node (ref "D28") (pin "25") (pinfunction "SDADC_CAP_25") (pintype "passive"))
    )
    (net (code "110") (name "Net-(D28-VAON_CAP)") (class "Default")
      (node (ref "C427") (pin "1") (pinfunction "1_1") (pintype "passive"))
      (node (ref "D28") (pin "13") (pinfunction "VAON_CAP_13") (pintype "passive"))
    )
    (net (code "111") (name "Net-(D28-VBAT)") (class "Default")
      (node (ref "D28") (pin "14") (pinfunction "VBAT_14") (pintype "passive"))
      (node (ref "R259") (pin "1") (pinfunction "1_1") (pintype "passive"))
    )
    (net (code "112") (name "Net-(D28-VBAT_CAP)") (class "Default")
      (node (ref "C425") (pin "1") (pinfunction "1_1") (pintype "passive"))
      (node (ref "D28") (pin "15") (pinfunction "VBAT_CAP_15") (pintype "passive"))
    )
    (net (code "113") (name "Net-(D28-VCORE_CAP)") (class "Default")
      (node (ref "C426") (pin "1") (pinfunction "1_1") (pintype "passive"))
      (node (ref "D28") (pin "17") (pinfunction "VCORE_CAP_17") (pintype "passive"))
    )
    (net (code "114") (name "Net-(D28-WAKEUP0)") (class "Default")
      (node (ref "D28") (pin "100") (pinfunction "WAKEUP0_100") (pintype "passive"))
      (node (ref "R249") (pin "2") (pinfunction "2_2") (pintype "passive"))
    )
    (net (code "115") (name "Net-(D28-WAKEUP1)") (class "Default")
      (node (ref "D28") (pin "99") (pinfunction "WAKEUP1_99") (pintype "passive"))
      (node (ref "R250") (pin "2") (pinfunction "2_2") (pintype "passive"))
    )
    (net (code "116") (name "Net-(D28-WAKEUP2)") (class "Default")
      (node (ref "D28") (pin "98") (pinfunction "WAKEUP2_98") (pintype "passive"))
      (node (ref "R252") (pin "2") (pinfunction "2_2") (pintype "passive"))
    )
    (net (code "117") (name "Net-(D29-COM3)") (class "Default")
      (node (ref "D29") (pin "4") (pinfunction "COM3_4") (pintype "passive"))
      (node (ref "R260") (pin "2") (pinfunction "2_2") (pintype "passive"))
    )
    (net (code "118") (name "Net-(D29-COM4)") (class "Default")
      (node (ref "D29") (pin "6") (pinfunction "COM4_6") (pintype "passive"))
      (node (ref "R261") (pin "2") (pinfunction "2_2") (pintype "passive"))
    )
    (net (code "119") (name "Net-(D29-COM5)") (class "Default")
      (node (ref "D29") (pin "7") (pinfunction "COM5_7") (pintype "passive"))
      (node (ref "R262") (pin "2") (pinfunction "2_2") (pintype "passive"))
    )
    (net (code "120") (name "Net-(D29-COM6)") (class "Default")
      (node (ref "D29") (pin "9") (pinfunction "COM6_9") (pintype "passive"))
      (node (ref "R263") (pin "2") (pinfunction "2_2") (pintype "passive"))
    )
    (net (code "121") (name "Net-(D29-EN#)") (class "Default")
      (node (ref "D29") (pin "17") (pinfunction "EN#_17") (pintype "passive"))
      (node (ref "R266") (pin "2") (pinfunction "2_2") (pintype "passive"))
    )
    (net (code "122") (name "Net-(D31-EN#)") (class "Default")
      (node (ref "D31") (pin "17") (pinfunction "EN#_17") (pintype "passive"))
      (node (ref "R284") (pin "2") (pinfunction "2_2") (pintype "passive"))
    )
    (net (code "123") (name "Net-(R202-Pad1)") (class "Default")
      (node (ref "R202") (pin "1") (pinfunction "1_1") (pintype "passive"))
      (node (ref "R251") (pin "2") (pinfunction "2_2") (pintype "passive"))
    )
    (net (code "124") (name "Net-(VD44-K)") (class "Default")
      (node (ref "R267") (pin "1") (pinfunction "1_1") (pintype "passive"))
      (node (ref "VD44") (pin "1") (pinfunction "K_1") (pintype "passive"))
    )
    (net (code "125") (name "Net-(VD44-REF)") (class "Default")
      (node (ref "C438") (pin "1") (pinfunction "1_1") (pintype "passive"))
      (node (ref "R272") (pin "1") (pinfunction "1_1") (pintype "passive"))
      (node (ref "R281") (pin "1") (pinfunction "1_1") (pintype "passive"))
      (node (ref "VD44") (pin "2") (pinfunction "REF_2") (pintype "passive"))
      (node (ref "VD45") (pin "1") (pinfunction "REF_1") (pintype "passive"))
    )
    (net (code "126") (name "Net-(VT10-B)") (class "Default")
      (node (ref "R106") (pin "1") (pinfunction "1_1") (pintype "passive"))
      (node (ref "VT10") (pin "1") (pinfunction "B_1") (pintype "passive"))
    )
    (net (code "127") (name "VCC5V0_DEVICE_S0") (class "Default")
      (node (ref "R203") (pin "1") (pinfunction "1_1") (pintype "passive"))
    )
    (net (code "128") (name "VCC5V0_SYS_S5") (class "Default")
      (node (ref "C436") (pin "2") (pinfunction "2_2") (pintype "passive"))
      (node (ref "D30") (pin "1") (pinfunction "IN_1") (pintype "passive"))
      (node (ref "D30") (pin "3") (pinfunction "EN_3") (pintype "passive"))
      (node (ref "R270") (pin "1") (pinfunction "1_1") (pintype "passive"))
    )
    (net (code "129") (name "VCC_1V8_S3") (class "Default")
      (node (ref "C586") (pin "1") (pinfunction "1_1") (pintype "passive"))
      (node (ref "D43") (pin "OE") (pinfunction "OE_OE") (pintype "passive"))
      (node (ref "D43") (pin "VCCA") (pinfunction "VCCA_VCCA") (pintype "passive"))
    )
    (net (code "130") (name "VCC_3V3_S0") (class "Default")
      (node (ref "R269") (pin "1") (pinfunction "1_1") (pintype "passive"))
    )
    (net (code "131") (name "unconnected-(D28-ADC_CH6-Pad28)") (class "Default")
      (node (ref "D28") (pin "28") (pinfunction "ADC_CH6_28") (pintype "passive+no_connect"))
    )
    (net (code "132") (name "unconnected-(D28-ADC_CH7-Pad29)") (class "Default")
      (node (ref "D28") (pin "29") (pinfunction "ADC_CH7_29") (pintype "passive+no_connect"))
    )
    (net (code "133") (name "unconnected-(D28-C0{slash}TMR32_OUT0{slash}UART3_RTS-Pad34)") (class "Default")
      (node (ref "D28") (pin "34") (pinfunction "C0/TMR32_OUT0/UART3_RTS_34") (pintype "passive+no_connect"))
    )
    (net (code "134") (name "unconnected-(D28-C1{slash}TMR32_OUT1{slash}UART3_DTR-Pad35)") (class "Default")
      (node (ref "D28") (pin "35") (pinfunction "C1/TMR32_OUT1/UART3_DTR_35") (pintype "passive+no_connect"))
    )
    (net (code "135") (name "unconnected-(D28-C2{slash}TMR32_OUT2{slash}UART4_CTS-Pad36)") (class "Default")
      (node (ref "D28") (pin "36") (pinfunction "C2/TMR32_OUT2/UART4_CTS_36") (pintype "passive+no_connect"))
    )
    (net (code "136") (name "unconnected-(D28-C3{slash}TMR32_OUT3{slash}UART4_DCD-Pad37)") (class "Default")
      (node (ref "D28") (pin "37") (pinfunction "C3/TMR32_OUT3/UART4_DCD_37") (pintype "passive+no_connect"))
    )
    (net (code "137") (name "unconnected-(D28-C4{slash}TMR32_EXTIN{slash}UART4_DSR-Pad38)") (class "Default")
      (node (ref "D28") (pin "38") (pinfunction "C4/TMR32_EXTIN/UART4_DSR_38") (pintype "passive+no_connect"))
    )
    (net (code "138") (name "unconnected-(D28-C5{slash}TMR0_EXTIN{slash}UART4_RI-Pad39)") (class "Default")
      (node (ref "D28") (pin "39") (pinfunction "C5/TMR0_EXTIN/UART4_RI_39") (pintype "passive+no_connect"))
    )
    (net (code "139") (name "unconnected-(D28-C6{slash}TMR0_OUT0{slash}UART4_RTS-Pad40)") (class "Default")
      (node (ref "D28") (pin "40") (pinfunction "C6/TMR0_OUT0/UART4_RTS_40") (pintype "passive+no_connect"))
    )
    (net (code "140") (name "unconnected-(D28-C7{slash}TMR0_OUT1{slash}UART4_DTR{slash}CLKOUT-Pad41)") (class "Default")
      (node (ref "D28") (pin "41") (pinfunction "C7/TMR0_OUT1/UART4_DTR/CLKOUT_41") (pintype "passive+no_connect"))
    )
    (net (code "141") (name "unconnected-(D28-C8{slash}TMR0_OUT2{slash}CAN0_RX-Pad42)") (class "Default")
      (node (ref "D28") (pin "42") (pinfunction "C8/TMR0_OUT2/CAN0_RX_42") (pintype "passive+no_connect"))
    )
    (net (code "142") (name "unconnected-(D28-C9{slash}TMR0_OUT3{slash}CAN0_TX-Pad43)") (class "Default")
      (node (ref "D28") (pin "43") (pinfunction "C9/TMR0_OUT3/CAN0_TX_43") (pintype "passive+no_connect"))
    )
    (net (code "143") (name "unconnected-(D28-C10{slash}TMR0_CCIA{slash}CAN1_RX-Pad44)") (class "Default")
      (node (ref "D28") (pin "44") (pinfunction "C10/TMR0_CCIA/CAN1_RX_44") (pintype "passive+no_connect"))
    )
    (net (code "144") (name "unconnected-(D28-C11{slash}TMR0_CCIB{slash}CAN1_TX-Pad45)") (class "Default")
      (node (ref "D28") (pin "45") (pinfunction "C11/TMR0_CCIB/CAN1_TX_45") (pintype "passive+no_connect"))
    )
    (net (code "145") (name "unconnected-(D28-C12{slash}I2C_SCL{slash}TMR1_EXTIN-Pad46)") (class "Default")
      (node (ref "D28") (pin "46") (pinfunction "C12/I2C_SCL/TMR1_EXTIN_46") (pintype "passive"))
    )
    (net (code "146") (name "unconnected-(D28-C13{slash}I2C_SDA{slash}TMR2_EXTIN-Pad47)") (class "Default")
      (node (ref "D28") (pin "47") (pinfunction "C13/I2C_SDA/TMR2_EXTIN_47") (pintype "passive"))
    )
    (net (code "147") (name "unconnected-(D28-C14{slash}TMR2_CCIA{slash}I2C_SCL-Pad48)") (class "Default")
      (node (ref "D28") (pin "48") (pinfunction "C14/TMR2_CCIA/I2C_SCL_48") (pintype "passive+no_connect"))
    )
    (net (code "148") (name "unconnected-(D28-C15{slash}TMR2_CCIB{slash}I2C_SDA-Pad49)") (class "Default")
      (node (ref "D28") (pin "49") (pinfunction "C15/TMR2_CCIB/I2C_SDA_49") (pintype "passive+no_connect"))
    )
    (net (code "149") (name "unconnected-(D28-CMP_INP0-Pad6)") (class "Default")
      (node (ref "D28") (pin "6") (pinfunction "CMP_INP0_6") (pintype "passive+no_connect"))
    )
    (net (code "150") (name "unconnected-(D28-CMP_INP1-Pad8)") (class "Default")
      (node (ref "D28") (pin "8") (pinfunction "CMP_INP1_8") (pintype "passive+no_connect"))
    )
    (net (code "151") (name "unconnected-(D28-USB_DN-Pad31)") (class "Default")
      (node (ref "D28") (pin "31") (pinfunction "USB_DN_31") (pintype "passive+no_connect"))
    )
    (net (code "152") (name "unconnected-(D28-USB_DP-Pad30)") (class "Default")
      (node (ref "D28") (pin "30") (pinfunction "USB_DP_30") (pintype "passive+no_connect"))
    )
    (net (code "153") (name "unconnected-(D28-~{CMP_INN0}-Pad5)") (class "Default")
      (node (ref "D28") (pin "5") (pinfunction "~{CMP_INN0}_5") (pintype "passive+no_connect"))
    )
    (net (code "154") (name "unconnected-(D28-~{CMP_INN1}-Pad7)") (class "Default")
      (node (ref "D28") (pin "7") (pinfunction "~{CMP_INN1}_7") (pintype "passive+no_connect"))
    )
    (net (code "155") (name "unconnected-(D29-N.C-Pad24)") (class "Default")
      (node (ref "D29") (pin "24") (pinfunction "N.C_24") (pintype "passive+no_connect"))
    )
    (net (code "156") (name "unconnected-(D30-NC-Pad4)") (class "Default")
      (node (ref "D30") (pin "4") (pinfunction "NC_4") (pintype "passive+no_connect"))
    )
    (net (code "157") (name "unconnected-(D31-N.C-Pad24)") (class "Default")
      (node (ref "D31") (pin "24") (pinfunction "N.C_24") (pintype "passive+no_connect"))
    )
    (net (code "158") (name "unconnected-(D43-PadA3)") (class "Default")
      (node (ref "D43") (pin "A3") (pinfunction "A3_A3") (pintype "passive+no_connect"))
    )
    (net (code "159") (name "unconnected-(D43-PadA4)") (class "Default")
      (node (ref "D43") (pin "A4") (pinfunction "A4_A4") (pintype "passive+no_connect"))
    )
    (net (code "160") (name "unconnected-(D43-PadB3)") (class "Default")
      (node (ref "D43") (pin "B3") (pinfunction "B3_B3") (pintype "passive+no_connect"))
    )
    (net (code "161") (name "unconnected-(D43-PadB4)") (class "Default")
      (node (ref "D43") (pin "B4") (pinfunction "B4_B4") (pintype "passive+no_connect"))
    )
  )
)
